# MCU.net
KiCad netlist of a schematic drawn in Altium Designer
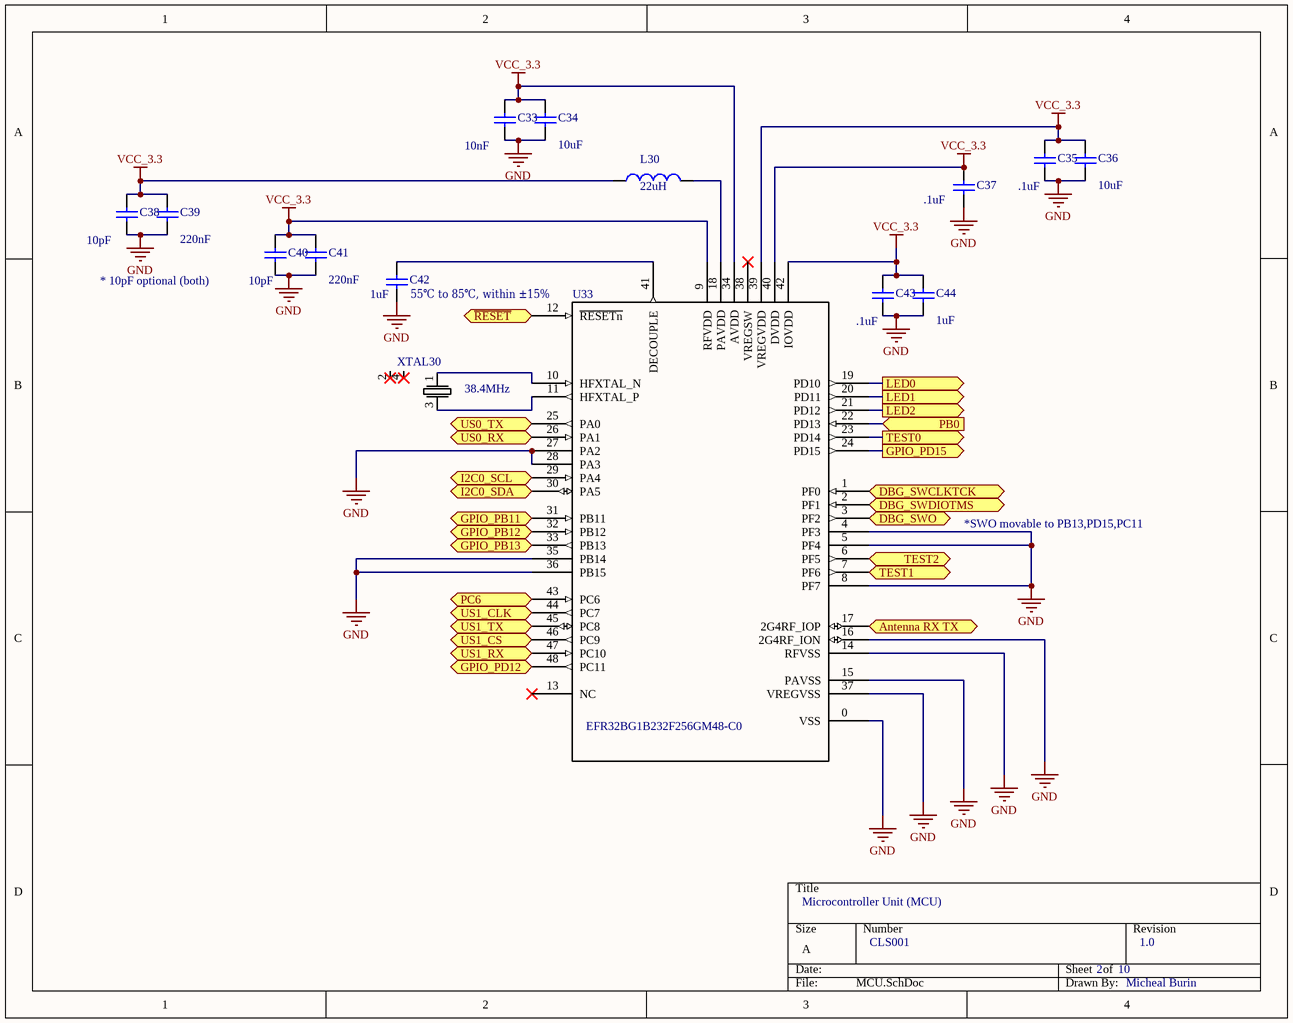
[diagram p0: MCU.SchDoc]

(export (version "E")
  (design (tool "Eeschema 10.0.6"))
  (components
    (comp (ref "C33")
      (value "10nF")
      (footprint "0805_CHIP_FP")
      (fields
        (field (name "MANUFACTURER") "Samsung Electro-Mechanics")
        (field (name "MANUFACTURER PART NUMBER") "CL21B103KAANNNC")
        (field (name "VENDOR PART NUMBER") "1276-2434-1-ND")
      )
      (libsource (lib "GenericSymbols") (part "Capacitor_unpolarized_0805"))
    )
    (comp (ref "C34")
      (value "10uF")
      (footprint "0805_CHIP_FP")
      (fields
        (field (name "MANUFACTURER") "Samsung Electro-Mechanics")
        (field (name "MANUFACTURER PART NUMBER") "CL21A106KPFNNNG")
        (field (name "VENDOR PART NUMBER") "1276-6456-1-ND")
      )
      (libsource (lib "GenericSymbols") (part "Capacitor_unpolarized_0805"))
    )
    (comp (ref "C35")
      (value ".1uF")
      (footprint "0805_CHIP_FP")
      (fields
        (field (name "MANUFACTURER") "Johanson Dielectrics Inc.")
        (field (name "MANUFACTURER PART NUMBER") "250R15W104KV4T")
        (field (name "VENDOR PART NUMBER") "709-1185-1-ND")
      )
      (libsource (lib "GenericSymbols") (part "Capacitor_unpolarized_0805"))
    )
    (comp (ref "C36")
      (value "10uF")
      (footprint "0805_CHIP_FP")
      (fields
        (field (name "MANUFACTURER") "Samsung Electro-Mechanics")
        (field (name "MANUFACTURER PART NUMBER") "CL21A106KPFNNNG")
        (field (name "VENDOR PART NUMBER") "1276-6456-1-ND")
      )
      (libsource (lib "GenericSymbols") (part "Capacitor_unpolarized_0805"))
    )
    (comp (ref "C37")
      (value ".1uF")
      (footprint "0805_CHIP_FP")
      (fields
        (field (name "MANUFACTURER") "Johanson Dielectrics Inc.")
        (field (name "MANUFACTURER PART NUMBER") "250R15W104KV4T")
        (field (name "VENDOR PART NUMBER") "709-1185-1-ND")
      )
      (libsource (lib "GenericSymbols") (part "Capacitor_unpolarized_0805"))
    )
    (comp (ref "C38")
      (value "10pF")
      (footprint "0805_CHIP_FP")
      (fields
        (field (name "MANUFACTURER") "Wurth Electronics Inc.")
        (field (name "MANUFACTURER PART NUMBER") "885012007028")
        (field (name "VENDOR PART NUMBER") "732-7827-1-ND")
      )
      (libsource (lib "GenericSymbols") (part "Capacitor_unpolarized_0805"))
    )
    (comp (ref "C39")
      (value "220nF")
      (footprint "0805_CHIP_FP")
      (fields
        (field (name "MANUFACTURER") "Wurth Electronics Inc.")
        (field (name "MANUFACTURER PART NUMBER") "885012207074")
        (field (name "VENDOR PART NUMBER") "732-7668-1-ND")
      )
      (libsource (lib "GenericSymbols") (part "Capacitor_unpolarized_0805"))
    )
    (comp (ref "C40")
      (value "10pF")
      (footprint "0805_CHIP_FP")
      (fields
        (field (name "MANUFACTURER") "Wurth Electronics Inc.")
        (field (name "MANUFACTURER PART NUMBER") "885012007028")
        (field (name "VENDOR PART NUMBER") "732-7827-1-ND")
      )
      (libsource (lib "GenericSymbols") (part "Capacitor_unpolarized_0805"))
    )
    (comp (ref "C41")
      (value "220nF")
      (footprint "0805_CHIP_FP")
      (fields
        (field (name "MANUFACTURER") "Wurth Electronics Inc.")
        (field (name "MANUFACTURER PART NUMBER") "885012207074")
        (field (name "VENDOR PART NUMBER") "732-7668-1-ND")
      )
      (libsource (lib "GenericSymbols") (part "Capacitor_unpolarized_0805"))
    )
    (comp (ref "C42")
      (value "1uF")
      (footprint "0805_CHIP_FP")
      (fields
        (field (name "MANUFACTURER") "Samsung Electro-Mechanics")
        (field (name "MANUFACTURER PART NUMBER") "CL21A105KOFNNNE")
        (field (name "VENDOR PART NUMBER") "1276-2888-1-ND")
      )
      (libsource (lib "GenericSymbols") (part "Capacitor_unpolarized_0805"))
    )
    (comp (ref "C43")
      (value ".1uF")
      (footprint "0805_CHIP_FP")
      (fields
        (field (name "MANUFACTURER") "Johanson Dielectrics Inc.")
        (field (name "MANUFACTURER PART NUMBER") "250R15W104KV4T")
        (field (name "VENDOR PART NUMBER") "709-1185-1-ND")
      )
      (libsource (lib "GenericSymbols") (part "Capacitor_unpolarized_0805"))
    )
    (comp (ref "C44")
      (value "1uF")
      (footprint "0805_CHIP_FP")
      (fields
        (field (name "MANUFACTURER") "Samsung Electro-Mechanics")
        (field (name "MANUFACTURER PART NUMBER") "CL21A105KOFNNNE")
        (field (name "VENDOR PART NUMBER") "1276-2888-1-ND")
      )
      (libsource (lib "GenericSymbols") (part "Capacitor_unpolarized_0805"))
    )
    (comp (ref "L30")
      (value "22uH")
      (footprint "0402_CHIP_FP")
      (description "Inductor")
      (fields
        (field (name "MANUFACTURER") "Murata Electronics North America")
        (field (name "MANUFACTURER PART NUMBER") "LQG15HS22NJ02D")
      )
      (libsource (lib "GenericSymbols") (part "Inductor"))
    )
    (comp (ref "U33")
      (value "EFR32BG1B232F256GM48-C0")
      (footprint "QFN127P600-8N")
      (description "EFR32BG1B232F256GM48-C0 48 pin")
      (fields (field (name "MF") "Silicon Labs") (field (name "VENDOR PART NUMBER") "634-EFR32BG232FGM48C"))
      (libsource (lib "EFR32BG1B232F256GM48-C0") (part "EFR32BG1B232F256GM48-C0"))
    )
    (comp (ref "XTAL30")
      (value "crystal_4_legged")
      (footprint "OSC-DFN140P160X55-4N")
      (description "crystal")
      (fields
        (field (name "MANUFACTURER") "CTS-Frequency Controls")
        (field (name "MANUFACTURER PART NUMBER") "402F38411CAR")
      )
      (libsource (lib "GenericSymbols") (part "crystal_4_legged"))
    )
  )
  (nets
    (net (code "1") (name "/Antenna RX TX") (class "Default")
      (node (ref "U33") (pin "17") (pinfunction "2G4RF_IOP_17") (pintype "bidirectional"))
    )
    (net (code "2") (name "/DBG_SWCLKTCK") (class "Default")
      (node (ref "U33") (pin "1") (pinfunction "PF0_1") (pintype "input"))
    )
    (net (code "3") (name "/DBG_SWDIOTMS") (class "Default")
      (node (ref "U33") (pin "2") (pinfunction "PF1_2") (pintype "input"))
    )
    (net (code "4") (name "/DBG_SWO") (class "Default")
      (node (ref "U33") (pin "3") (pinfunction "PF2_3") (pintype "output"))
    )
    (net (code "5") (name "/GPIO_PB11") (class "Default")
      (node (ref "U33") (pin "31") (pinfunction "PB11_31") (pintype "input"))
    )
    (net (code "6") (name "/GPIO_PB12") (class "Default")
      (node (ref "U33") (pin "32") (pinfunction "PB12_32") (pintype "input"))
    )
    (net (code "7") (name "/GPIO_PB13") (class "Default")
      (node (ref "U33") (pin "33") (pinfunction "PB13_33") (pintype "output"))
    )
    (net (code "8") (name "/GPIO_PD12") (class "Default")
      (node (ref "U33") (pin "48") (pinfunction "PC11_48") (pintype "output"))
    )
    (net (code "9") (name "/GPIO_PD15") (class "Default")
      (node (ref "U33") (pin "24") (pinfunction "PD15_24") (pintype "output"))
    )
    (net (code "10") (name "/I2C0_SCL") (class "Default")
      (node (ref "U33") (pin "29") (pinfunction "PA4_29") (pintype "input"))
    )
    (net (code "11") (name "/I2C0_SDA") (class "Default")
      (node (ref "U33") (pin "30") (pinfunction "PA5_30") (pintype "bidirectional"))
    )
    (net (code "12") (name "/LED0") (class "Default")
      (node (ref "U33") (pin "19") (pinfunction "PD10_19") (pintype "output"))
    )
    (net (code "13") (name "/LED1") (class "Default")
      (node (ref "U33") (pin "20") (pinfunction "PD11_20") (pintype "output"))
    )
    (net (code "14") (name "/LED2") (class "Default")
      (node (ref "U33") (pin "21") (pinfunction "PD12_21") (pintype "output"))
    )
    (net (code "15") (name "/PB0") (class "Default")
      (node (ref "U33") (pin "22") (pinfunction "PD13_22") (pintype "input"))
    )
    (net (code "16") (name "/PC6") (class "Default")
      (node (ref "U33") (pin "43") (pinfunction "PC6_43") (pintype "input"))
    )
    (net (code "17") (name "/TEST0") (class "Default")
      (node (ref "U33") (pin "23") (pinfunction "PD14_23") (pintype "output"))
    )
    (net (code "18") (name "/TEST1") (class "Default")
      (node (ref "U33") (pin "7") (pinfunction "PF6_7") (pintype "output"))
    )
    (net (code "19") (name "/TEST2") (class "Default")
      (node (ref "U33") (pin "6") (pinfunction "PF5_6") (pintype "output"))
    )
    (net (code "20") (name "/US0_RX") (class "Default")
      (node (ref "U33") (pin "26") (pinfunction "PA1_26") (pintype "input"))
    )
    (net (code "21") (name "/US0_TX") (class "Default")
      (node (ref "U33") (pin "25") (pinfunction "PA0_25") (pintype "output"))
    )
    (net (code "22") (name "/US1_CLK") (class "Default")
      (node (ref "U33") (pin "44") (pinfunction "PC7_44") (pintype "output"))
    )
    (net (code "23") (name "/US1_CS") (class "Default")
      (node (ref "U33") (pin "46") (pinfunction "PC9_46") (pintype "output"))
    )
    (net (code "24") (name "/US1_RX") (class "Default")
      (node (ref "U33") (pin "47") (pinfunction "PC10_47") (pintype "input"))
    )
    (net (code "25") (name "/US1_TX") (class "Default")
      (node (ref "U33") (pin "45") (pinfunction "PC8_45") (pintype "bidirectional"))
    )
    (net (code "26") (name "/~{RESET}") (class "Default")
      (node (ref "U33") (pin "12") (pinfunction "~{RESETn}_12") (pintype "input"))
    )
    (net (code "27") (name "GND") (class "Default")
      (node (ref "C33") (pin "2") (pinfunction "2_2") (pintype "passive"))
      (node (ref "C34") (pin "2") (pinfunction "2_2") (pintype "passive"))
      (node (ref "C35") (pin "1") (pinfunction "1_1") (pintype "passive"))
      (node (ref "C36") (pin "1") (pinfunction "1_1") (pintype "passive"))
      (node (ref "C37") (pin "1") (pinfunction "1_1") (pintype "passive"))
      (node (ref "C38") (pin "1") (pinfunction "1_1") (pintype "passive"))
      (node (ref "C39") (pin "1") (pinfunction "1_1") (pintype "passive"))
      (node (ref "C40") (pin "1") (pinfunction "1_1") (pintype "passive"))
      (node (ref "C41") (pin "1") (pinfunction "1_1") (pintype "passive"))
      (node (ref "C42") (pin "1") (pinfunction "1_1") (pintype "passive"))
      (node (ref "C43") (pin "1") (pinfunction "1_1") (pintype "passive"))
      (node (ref "C44") (pin "1") (pinfunction "1_1") (pintype "passive"))
      (node (ref "U33") (pin "0") (pinfunction "VSS_0") (pintype "power_in"))
      (node (ref "U33") (pin "14") (pinfunction "RFVSS_14") (pintype "power_in"))
      (node (ref "U33") (pin "15") (pinfunction "PAVSS_15") (pintype "power_in"))
      (node (ref "U33") (pin "16") (pinfunction "2G4RF_ION_16") (pintype "bidirectional"))
      (node (ref "U33") (pin "27") (pinfunction "PA2_27") (pintype "passive"))
      (node (ref "U33") (pin "28") (pinfunction "PA3_28") (pintype "passive"))
      (node (ref "U33") (pin "35") (pinfunction "PB14_35") (pintype "passive"))
      (node (ref "U33") (pin "36") (pinfunction "PB15_36") (pintype "passive"))
      (node (ref "U33") (pin "37") (pinfunction "VREGVSS_37") (pintype "power_in"))
      (node (ref "U33") (pin "4") (pinfunction "PF3_4") (pintype "passive"))
      (node (ref "U33") (pin "5") (pinfunction "PF4_5") (pintype "passive"))
      (node (ref "U33") (pin "8") (pinfunction "PF7_8") (pintype "passive"))
    )
    (net (code "28") (name "Net-(U33-DECOUPLE)") (class "Default")
      (node (ref "C42") (pin "2") (pinfunction "2_2") (pintype "passive"))
      (node (ref "U33") (pin "41") (pinfunction "DECOUPLE_41") (pintype "output"))
    )
    (net (code "29") (name "Net-(U33-HFXTAL_N)") (class "Default")
      (node (ref "U33") (pin "10") (pinfunction "HFXTAL_N_10") (pintype "input"))
      (node (ref "XTAL30") (pin "1") (pintype "passive"))
    )
    (net (code "30") (name "Net-(U33-HFXTAL_P)") (class "Default")
      (node (ref "U33") (pin "11") (pinfunction "HFXTAL_P_11") (pintype "output"))
      (node (ref "XTAL30") (pin "3") (pintype "passive"))
    )
    (net (code "31") (name "Net-(U33-PAVDD)") (class "Default")
      (node (ref "L30") (pin "2") (pinfunction "2_2") (pintype "passive"))
      (node (ref "U33") (pin "18") (pinfunction "PAVDD_18") (pintype "power_in"))
    )
    (net (code "32") (name "VCC_3.3") (class "Default")
      (node (ref "C33") (pin "1") (pinfunction "1_1") (pintype "passive"))
      (node (ref "C34") (pin "1") (pinfunction "1_1") (pintype "passive"))
      (node (ref "C35") (pin "2") (pinfunction "2_2") (pintype "passive"))
      (node (ref "C36") (pin "2") (pinfunction "2_2") (pintype "passive"))
      (node (ref "C37") (pin "2") (pinfunction "2_2") (pintype "passive"))
      (node (ref "C38") (pin "2") (pinfunction "2_2") (pintype "passive"))
      (node (ref "C39") (pin "2") (pinfunction "2_2") (pintype "passive"))
      (node (ref "C40") (pin "2") (pinfunction "2_2") (pintype "passive"))
      (node (ref "C41") (pin "2") (pinfunction "2_2") (pintype "passive"))
      (node (ref "C43") (pin "2") (pinfunction "2_2") (pintype "passive"))
      (node (ref "C44") (pin "2") (pinfunction "2_2") (pintype "passive"))
      (node (ref "L30") (pin "1") (pinfunction "1_1") (pintype "passive"))
      (node (ref "U33") (pin "34") (pinfunction "AVDD_34") (pintype "power_in"))
      (node (ref "U33") (pin "39") (pinfunction "VREGVDD_39") (pintype "power_in"))
      (node (ref "U33") (pin "40") (pinfunction "DVDD_40") (pintype "power_in"))
      (node (ref "U33") (pin "42") (pinfunction "IOVDD_42") (pintype "power_in"))
      (node (ref "U33") (pin "9") (pinfunction "RFVDD_9") (pintype "power_in"))
    )
    (net (code "33") (name "unconnected-(U33-NC-Pad13)") (class "Default")
      (node (ref "U33") (pin "13") (pinfunction "NC_13") (pintype "passive+no_connect"))
    )
    (net (code "34") (name "unconnected-(U33-VREGSW-Pad38)") (class "Default")
      (node (ref "U33") (pin "38") (pinfunction "VREGSW_38") (pintype "power_in+no_connect"))
    )
    (net (code "35") (name "unconnected-(XTAL30-Pad2)") (class "Default")
      (node (ref "XTAL30") (pin "2") (pintype "passive+no_connect"))
    )
    (net (code "36") (name "unconnected-(XTAL30-Pad4)") (class "Default")
      (node (ref "XTAL30") (pin "4") (pintype "passive+no_connect"))
    )
  )
)
